# terminal_board.net
KiCad netlist of a schematic drawn in EAGLE
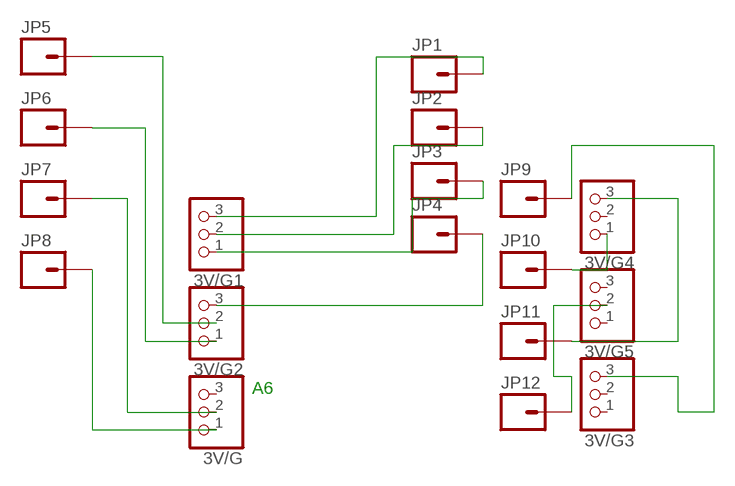
[diagram p0: schematic, sheet 1]

(export (version "E")
  (design (tool "Eeschema 10.0.6"))
  (components
    (comp (ref "3V/G")
      (value "PINHD-1X3CB")
      (footprint "eagle-import:1X03-CLEANBIG")
      (libsource (lib "eagle-import") (part "PINHD-1X3CB"))
    )
    (comp (ref "3V/G1")
      (value "PINHD-1X3CB")
      (footprint "eagle-import:1X03-CLEANBIG")
      (libsource (lib "eagle-import") (part "PINHD-1X3CB"))
    )
    (comp (ref "3V/G2")
      (value "PINHD-1X3CB")
      (footprint "eagle-import:1X03-CLEANBIG")
      (libsource (lib "eagle-import") (part "PINHD-1X3CB"))
    )
    (comp (ref "3V/G3")
      (value "PINHD-1X3CB")
      (footprint "eagle-import:1X03-CLEANBIG")
      (libsource (lib "eagle-import") (part "PINHD-1X3CB"))
    )
    (comp (ref "3V/G4")
      (value "PINHD-1X3CB")
      (footprint "eagle-import:1X03-CLEANBIG")
      (libsource (lib "eagle-import") (part "PINHD-1X3CB"))
    )
    (comp (ref "3V/G5")
      (value "PINHD-1X3CB")
      (footprint "eagle-import:1X03-CLEANBIG")
      (libsource (lib "eagle-import") (part "PINHD-1X3CB"))
    )
    (comp (ref "JP1")
      (value "M01PTH_2MM")
      (footprint "eagle-import:1X01_2MM")
      (libsource (lib "eagle-import") (part "M01PTH_2MM"))
    )
    (comp (ref "JP2")
      (value "M01PTH_2MM")
      (footprint "eagle-import:1X01_2MM")
      (libsource (lib "eagle-import") (part "M01PTH_2MM"))
    )
    (comp (ref "JP3")
      (value "M01PTH_2MM")
      (footprint "eagle-import:1X01_2MM")
      (libsource (lib "eagle-import") (part "M01PTH_2MM"))
    )
    (comp (ref "JP4")
      (value "M01PTH_2MM")
      (footprint "eagle-import:1X01_2MM")
      (libsource (lib "eagle-import") (part "M01PTH_2MM"))
    )
    (comp (ref "JP5")
      (value "M01PTH_2MM")
      (footprint "eagle-import:1X01_2MM")
      (libsource (lib "eagle-import") (part "M01PTH_2MM"))
    )
    (comp (ref "JP6")
      (value "M01PTH_2MM")
      (footprint "eagle-import:1X01_2MM")
      (libsource (lib "eagle-import") (part "M01PTH_2MM"))
    )
    (comp (ref "JP7")
      (value "M01PTH_2MM")
      (footprint "eagle-import:1X01_2MM")
      (libsource (lib "eagle-import") (part "M01PTH_2MM"))
    )
    (comp (ref "JP8")
      (value "M01PTH_2MM")
      (footprint "eagle-import:1X01_2MM")
      (libsource (lib "eagle-import") (part "M01PTH_2MM"))
    )
    (comp (ref "JP9")
      (value "M01PTH_2MM")
      (footprint "eagle-import:1X01_2MM")
      (libsource (lib "eagle-import") (part "M01PTH_2MM"))
    )
    (comp (ref "JP10")
      (value "M01PTH_2MM")
      (footprint "eagle-import:1X01_2MM")
      (libsource (lib "eagle-import") (part "M01PTH_2MM"))
    )
    (comp (ref "JP11")
      (value "M01PTH_2MM")
      (footprint "eagle-import:1X01_2MM")
      (libsource (lib "eagle-import") (part "M01PTH_2MM"))
    )
    (comp (ref "JP12")
      (value "M01PTH_2MM")
      (footprint "eagle-import:1X01_2MM")
      (libsource (lib "eagle-import") (part "M01PTH_2MM"))
    )
  )
  (nets
    (net (code "1") (name "Net-(3V/G-Pad1)") (class "Default")
      (node (ref "3V/G") (pin "1") (pinfunction "1_1") (pintype "passive"))
      (node (ref "JP8") (pin "1") (pinfunction "1_1") (pintype "passive"))
    )
    (net (code "2") (name "Net-(3V/G-Pad2)") (class "Default")
      (node (ref "3V/G") (pin "2") (pinfunction "2_2") (pintype "passive"))
      (node (ref "JP7") (pin "1") (pinfunction "1_1") (pintype "passive"))
    )
    (net (code "3") (name "Net-(3V/G1-Pad1)") (class "Default")
      (node (ref "3V/G1") (pin "1") (pinfunction "1_1") (pintype "passive"))
      (node (ref "JP3") (pin "1") (pinfunction "1_1") (pintype "passive"))
    )
    (net (code "4") (name "Net-(3V/G1-Pad2)") (class "Default")
      (node (ref "3V/G1") (pin "2") (pinfunction "2_2") (pintype "passive"))
      (node (ref "JP2") (pin "1") (pinfunction "1_1") (pintype "passive"))
    )
    (net (code "5") (name "Net-(3V/G1-Pad3)") (class "Default")
      (node (ref "3V/G1") (pin "3") (pinfunction "3_3") (pintype "passive"))
      (node (ref "JP1") (pin "1") (pinfunction "1_1") (pintype "passive"))
    )
    (net (code "6") (name "Net-(3V/G2-Pad1)") (class "Default")
      (node (ref "3V/G2") (pin "1") (pinfunction "1_1") (pintype "passive"))
      (node (ref "JP6") (pin "1") (pinfunction "1_1") (pintype "passive"))
    )
    (net (code "7") (name "Net-(3V/G2-Pad2)") (class "Default")
      (node (ref "3V/G2") (pin "2") (pinfunction "2_2") (pintype "passive"))
      (node (ref "JP5") (pin "1") (pinfunction "1_1") (pintype "passive"))
    )
    (net (code "8") (name "Net-(3V/G2-Pad3)") (class "Default")
      (node (ref "3V/G2") (pin "3") (pinfunction "3_3") (pintype "passive"))
      (node (ref "JP4") (pin "1") (pinfunction "1_1") (pintype "passive"))
    )
    (net (code "9") (name "Net-(3V/G3-Pad3)") (class "Default")
      (node (ref "3V/G3") (pin "3") (pinfunction "3_3") (pintype "passive"))
      (node (ref "JP9") (pin "1") (pinfunction "1_1") (pintype "passive"))
    )
    (net (code "10") (name "Net-(3V/G4-Pad1)") (class "Default")
      (node (ref "3V/G4") (pin "1") (pinfunction "1_1") (pintype "passive"))
      (node (ref "JP10") (pin "1") (pinfunction "1_1") (pintype "passive"))
    )
    (net (code "11") (name "Net-(3V/G4-Pad3)") (class "Default")
      (node (ref "3V/G4") (pin "3") (pinfunction "3_3") (pintype "passive"))
      (node (ref "JP11") (pin "1") (pinfunction "1_1") (pintype "passive"))
    )
    (net (code "12") (name "Net-(3V/G5-Pad2)") (class "Default")
      (node (ref "3V/G5") (pin "2") (pinfunction "2_2") (pintype "passive"))
      (node (ref "JP12") (pin "1") (pinfunction "1_1") (pintype "passive"))
    )
    (net (code "13") (name "unconnected-(3V/G-Pad3)") (class "Default")
      (node (ref "3V/G") (pin "3") (pinfunction "3_3") (pintype "passive"))
    )
    (net (code "14") (name "unconnected-(3V/G3-Pad1)") (class "Default")
      (node (ref "3V/G3") (pin "1") (pinfunction "1_1") (pintype "passive"))
    )
    (net (code "15") (name "unconnected-(3V/G3-Pad2)") (class "Default")
      (node (ref "3V/G3") (pin "2") (pinfunction "2_2") (pintype "passive"))
    )
    (net (code "16") (name "unconnected-(3V/G4-Pad2)") (class "Default")
      (node (ref "3V/G4") (pin "2") (pinfunction "2_2") (pintype "passive"))
    )
    (net (code "17") (name "unconnected-(3V/G5-Pad1)") (class "Default")
      (node (ref "3V/G5") (pin "1") (pinfunction "1_1") (pintype "passive"))
    )
    (net (code "18") (name "unconnected-(3V/G5-Pad3)") (class "Default")
      (node (ref "3V/G5") (pin "3") (pinfunction "3_3") (pintype "passive"))
    )
  )
)
